# gesture_control_robot_rx.net
KiCad netlist of a schematic drawn in EAGLE
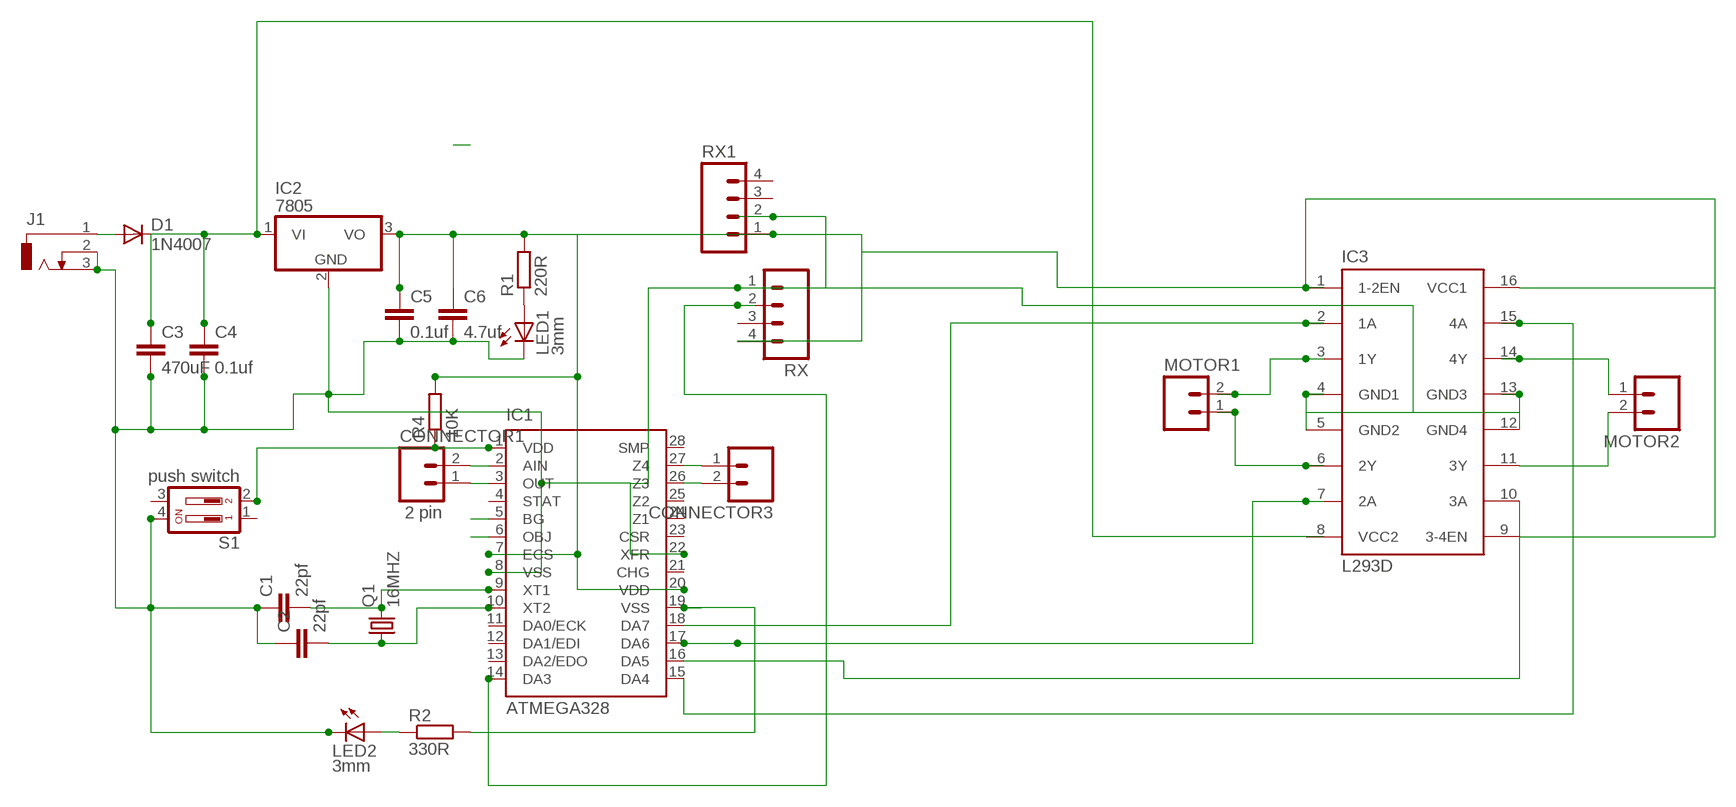
[diagram p0: schematic, sheet 1]

(export (version "E")
  (design (tool "Eeschema 10.0.6"))
  (components
    (comp (ref "C1")
      (value "22pf")
      (footprint "eagle-import:C2.5-2")
      (libsource (lib "eagle-import") (part "C2.5/2"))
    )
    (comp (ref "C2")
      (value "22pf")
      (footprint "eagle-import:C2.5-2")
      (libsource (lib "eagle-import") (part "C2.5/2"))
    )
    (comp (ref "C3")
      (value "470uF")
      (footprint "eagle-import:C2.5-2")
      (libsource (lib "eagle-import") (part "C2.5/2"))
    )
    (comp (ref "C4")
      (value "0.1uf")
      (footprint "eagle-import:C2.5-2")
      (libsource (lib "eagle-import") (part "C2.5/2"))
    )
    (comp (ref "C5")
      (value "0.1uf")
      (footprint "eagle-import:C2.5-2")
      (libsource (lib "eagle-import") (part "C2.5/2"))
    )
    (comp (ref "C6")
      (value "4.7uf")
      (footprint "eagle-import:C2.5-2")
      (libsource (lib "eagle-import") (part "C2.5/2"))
    )
    (comp (ref "CONNECTOR1")
      (value "2 pin")
      (footprint "eagle-import:02P")
      (fields (field (name "OC_FARNELL") "unknown") (field (name "OC_NEWARK") "unknown"))
      (libsource (lib "eagle-import") (part "M02"))
    )
    (comp (ref "CONNECTOR3")
      (value "M02")
      (footprint "eagle-import:02P")
      (fields (field (name "OC_FARNELL") "unknown") (field (name "OC_NEWARK") "unknown"))
      (libsource (lib "eagle-import") (part "M02"))
    )
    (comp (ref "D1")
      (value "1N4007")
      (footprint "eagle-import:DO41-10")
      (libsource (lib "eagle-import") (part "1N4004"))
    )
    (comp (ref "IC1")
      (value "ATMEGA328")
      (footprint "eagle-import:DIL28-3")
      (libsource (lib "eagle-import") (part "QT9701BD"))
    )
    (comp (ref "IC2")
      (value "7805")
      (footprint "eagle-import:TO220V")
      (libsource (lib "eagle-import") (part "78TV6"))
    )
    (comp (ref "IC3")
      (value "L293D")
      (footprint "eagle-import:DIL16")
      (libsource (lib "eagle-import") (part "L293D"))
    )
    (comp (ref "J1")
      (value "DCJ0303")
      (footprint "eagle-import:DCJ0303")
      (libsource (lib "eagle-import") (part "DCJ0303"))
    )
    (comp (ref "LED1")
      (value "3mm")
      (footprint "eagle-import:LED3MM")
      (libsource (lib "eagle-import") (part "LED3MM"))
    )
    (comp (ref "LED2")
      (value "3mm")
      (footprint "eagle-import:LED3MM")
      (libsource (lib "eagle-import") (part "LED3MM"))
    )
    (comp (ref "MOTOR1")
      (value "M02")
      (footprint "eagle-import:02P")
      (fields (field (name "OC_FARNELL") "unknown") (field (name "OC_NEWARK") "unknown"))
      (libsource (lib "eagle-import") (part "M02"))
    )
    (comp (ref "MOTOR2")
      (value "M02")
      (footprint "eagle-import:02P")
      (libsource (lib "eagle-import") (part "M02"))
    )
    (comp (ref "Q1")
      (value "16MHZ")
      (footprint "eagle-import:HC49_S")
      (libsource (lib "eagle-import") (part "CRYSTALHC49S"))
    )
    (comp (ref "R1")
      (value "220R")
      (footprint "eagle-import:0207_10")
      (libsource (lib "eagle-import") (part "R-EU_0207/10"))
    )
    (comp (ref "R2")
      (value "330R")
      (footprint "eagle-import:0207_10")
      (libsource (lib "eagle-import") (part "R-EU_0207/10"))
    )
    (comp (ref "R4")
      (value "10K")
      (footprint "eagle-import:0207_10")
      (libsource (lib "eagle-import") (part "R-EU_0207/10"))
    )
    (comp (ref "RX")
      (value "M04")
      (footprint "eagle-import:04P")
      (libsource (lib "eagle-import") (part "M04"))
    )
    (comp (ref "RX1")
      (value "M04")
      (footprint "eagle-import:04P")
      (fields (field (name "OC_FARNELL") "unknown") (field (name "OC_NEWARK") "unknown"))
      (libsource (lib "eagle-import") (part "M04"))
    )
    (comp (ref "S1")
      (value "push switch")
      (footprint "eagle-import:DP-02")
      (fields (field (name "MPN") "MCDP02"))
      (libsource (lib "eagle-import") (part "DP02"))
    )
  )
  (nets
    (net (code "1") (name "Net-(D1-PadA)") (class "Default")
      (node (ref "D1") (pin "A") (pinfunction "A_A") (pintype "passive"))
      (node (ref "J1") (pin "1") (pinfunction "1_1") (pintype "passive"))
    )
    (net (code "2") (name "Net-(IC1-AIN)") (class "Default")
      (node (ref "CONNECTOR1") (pin "2") (pinfunction "2_2") (pintype "passive"))
      (node (ref "IC1") (pin "2") (pinfunction "AIN_2") (pintype "input"))
    )
    (net (code "3") (name "Net-(IC1-DA3)") (class "Default")
      (node (ref "IC1") (pin "14") (pinfunction "DA3_14") (pintype "output"))
      (node (ref "RX") (pin "2") (pinfunction "2_2") (pintype "passive"))
    )
    (net (code "4") (name "Net-(IC1-DA4)") (class "Default")
      (node (ref "IC1") (pin "15") (pinfunction "DA4_15") (pintype "output"))
      (node (ref "IC3") (pin "15") (pinfunction "4A_15") (pintype "input"))
    )
    (net (code "5") (name "Net-(IC1-DA5)") (class "Default")
      (node (ref "IC1") (pin "16") (pinfunction "DA5_16") (pintype "output"))
      (node (ref "IC3") (pin "10") (pinfunction "3A_10") (pintype "input"))
    )
    (net (code "6") (name "Net-(IC1-DA6)") (class "Default")
      (node (ref "IC1") (pin "17") (pinfunction "DA6_17") (pintype "output"))
      (node (ref "IC3") (pin "7") (pinfunction "2A_7") (pintype "input"))
    )
    (net (code "7") (name "Net-(IC1-DA7)") (class "Default")
      (node (ref "IC1") (pin "18") (pinfunction "DA7_18") (pintype "output"))
      (node (ref "IC3") (pin "2") (pinfunction "1A_2") (pintype "input"))
    )
    (net (code "8") (name "Net-(IC1-ECS)") (class "Default")
      (node (ref "C5") (pin "1") (pinfunction "1_1") (pintype "passive"))
      (node (ref "C6") (pin "1") (pinfunction "1_1") (pintype "passive"))
      (node (ref "IC1") (pin "20") (pinfunction "VDD_20") (pintype "input"))
      (node (ref "IC1") (pin "7") (pinfunction "ECS_7") (pintype "output"))
      (node (ref "IC2") (pin "3") (pinfunction "VO_3") (pintype "passive"))
      (node (ref "IC3") (pin "1") (pinfunction "1-2EN_1") (pintype "input"))
      (node (ref "IC3") (pin "16") (pinfunction "VCC1_16") (pintype "power_in"))
      (node (ref "IC3") (pin "9") (pinfunction "3-4EN_9") (pintype "input"))
      (node (ref "R1") (pin "2") (pinfunction "2_2") (pintype "passive"))
      (node (ref "R4") (pin "2") (pinfunction "2_2") (pintype "passive"))
      (node (ref "RX") (pin "4") (pinfunction "4_4") (pintype "passive"))
      (node (ref "RX1") (pin "1") (pinfunction "1_1") (pintype "passive"))
    )
    (net (code "9") (name "Net-(IC1-OUT)") (class "Default")
      (node (ref "CONNECTOR1") (pin "1") (pinfunction "1_1") (pintype "passive"))
      (node (ref "IC1") (pin "3") (pinfunction "OUT_3") (pintype "output"))
    )
    (net (code "10") (name "Net-(IC1-VDD-Pad1)") (class "Default")
      (node (ref "IC1") (pin "1") (pinfunction "VDD_1") (pintype "input"))
      (node (ref "R4") (pin "1") (pinfunction "1_1") (pintype "passive"))
      (node (ref "S1") (pin "2") (pinfunction "2_2") (pintype "passive"))
    )
    (net (code "11") (name "Net-(IC1-VSS-Pad19)") (class "Default")
      (node (ref "IC1") (pin "19") (pinfunction "VSS_19") (pintype "input"))
      (node (ref "R2") (pin "2") (pinfunction "2_2") (pintype "passive"))
    )
    (net (code "12") (name "Net-(IC1-XFR)") (class "Default")
      (node (ref "C1") (pin "1") (pinfunction "1_1") (pintype "passive"))
      (node (ref "C2") (pin "1") (pinfunction "1_1") (pintype "passive"))
      (node (ref "C3") (pin "2") (pinfunction "2_2") (pintype "passive"))
      (node (ref "C4") (pin "2") (pinfunction "2_2") (pintype "passive"))
      (node (ref "C5") (pin "2") (pinfunction "2_2") (pintype "passive"))
      (node (ref "C6") (pin "2") (pinfunction "2_2") (pintype "passive"))
      (node (ref "IC1") (pin "22") (pinfunction "XFR_22") (pintype "output"))
      (node (ref "IC1") (pin "8") (pinfunction "VSS_8") (pintype "input"))
      (node (ref "IC2") (pin "2") (pinfunction "GND_2") (pintype "passive"))
      (node (ref "IC3") (pin "12") (pinfunction "GND4_12") (pintype "power_in"))
      (node (ref "IC3") (pin "13") (pinfunction "GND3_13") (pintype "power_in"))
      (node (ref "IC3") (pin "4") (pinfunction "GND1_4") (pintype "power_in"))
      (node (ref "IC3") (pin "5") (pinfunction "GND2_5") (pintype "power_in"))
      (node (ref "J1") (pin "2") (pinfunction "2_2") (pintype "passive"))
      (node (ref "J1") (pin "3") (pinfunction "3_3") (pintype "passive"))
      (node (ref "LED1") (pin "K") (pinfunction "C_K") (pintype "passive"))
      (node (ref "LED2") (pin "K") (pinfunction "C_K") (pintype "passive"))
      (node (ref "RX") (pin "1") (pinfunction "1_1") (pintype "passive"))
      (node (ref "RX1") (pin "2") (pinfunction "2_2") (pintype "passive"))
      (node (ref "S1") (pin "4") (pinfunction "4_4") (pintype "passive"))
    )
    (net (code "13") (name "Net-(IC1-XT1)") (class "Default")
      (node (ref "C1") (pin "2") (pinfunction "2_2") (pintype "passive"))
      (node (ref "IC1") (pin "9") (pinfunction "XT1_9") (pintype "input"))
      (node (ref "Q1") (pin "2") (pinfunction "2_2") (pintype "passive"))
    )
    (net (code "14") (name "Net-(IC1-XT2)") (class "Default")
      (node (ref "C2") (pin "2") (pinfunction "2_2") (pintype "passive"))
      (node (ref "IC1") (pin "10") (pinfunction "XT2_10") (pintype "output"))
      (node (ref "Q1") (pin "1") (pinfunction "1_1") (pintype "passive"))
    )
    (net (code "15") (name "Net-(IC1-Z3)") (class "Default")
      (node (ref "CONNECTOR3") (pin "2") (pinfunction "2_2") (pintype "passive"))
      (node (ref "IC1") (pin "26") (pinfunction "Z3_26") (pintype "output"))
    )
    (net (code "16") (name "Net-(IC1-Z4)") (class "Default")
      (node (ref "CONNECTOR3") (pin "1") (pinfunction "1_1") (pintype "passive"))
      (node (ref "IC1") (pin "27") (pinfunction "Z4_27") (pintype "output"))
    )
    (net (code "17") (name "Net-(IC2-VI)") (class "Default")
      (node (ref "C3") (pin "1") (pinfunction "1_1") (pintype "passive"))
      (node (ref "C4") (pin "1") (pinfunction "1_1") (pintype "passive"))
      (node (ref "D1") (pin "C") (pinfunction "C_C") (pintype "passive"))
      (node (ref "IC2") (pin "1") (pinfunction "VI_1") (pintype "input"))
      (node (ref "IC3") (pin "8") (pinfunction "VCC2_8") (pintype "power_in"))
    )
    (net (code "18") (name "Net-(IC3-1Y)") (class "Default")
      (node (ref "IC3") (pin "3") (pinfunction "1Y_3") (pintype "output"))
      (node (ref "MOTOR1") (pin "2") (pinfunction "2_2") (pintype "passive"))
    )
    (net (code "19") (name "Net-(IC3-2Y)") (class "Default")
      (node (ref "IC3") (pin "6") (pinfunction "2Y_6") (pintype "output"))
      (node (ref "MOTOR1") (pin "1") (pinfunction "1_1") (pintype "passive"))
    )
    (net (code "20") (name "Net-(IC3-3Y)") (class "Default")
      (node (ref "IC3") (pin "11") (pinfunction "3Y_11") (pintype "output"))
      (node (ref "MOTOR2") (pin "2") (pinfunction "2_2") (pintype "passive"))
    )
    (net (code "21") (name "Net-(IC3-4Y)") (class "Default")
      (node (ref "IC3") (pin "14") (pinfunction "4Y_14") (pintype "output"))
      (node (ref "MOTOR2") (pin "1") (pinfunction "1_1") (pintype "passive"))
    )
    (net (code "22") (name "Net-(LED1-PadA)") (class "Default")
      (node (ref "LED1") (pin "A") (pinfunction "A_A") (pintype "passive"))
      (node (ref "R1") (pin "1") (pinfunction "1_1") (pintype "passive"))
    )
    (net (code "23") (name "Net-(LED2-PadA)") (class "Default")
      (node (ref "LED2") (pin "A") (pinfunction "A_A") (pintype "passive"))
      (node (ref "R2") (pin "1") (pinfunction "1_1") (pintype "passive"))
    )
    (net (code "24") (name "unconnected-(IC1-BG-Pad5)") (class "Default")
      (node (ref "IC1") (pin "5") (pinfunction "BG_5") (pintype "input"))
    )
    (net (code "25") (name "unconnected-(IC1-CHG-Pad21)") (class "Default")
      (node (ref "IC1") (pin "21") (pinfunction "CHG_21") (pintype "output"))
    )
    (net (code "26") (name "unconnected-(IC1-CSR-Pad23)") (class "Default")
      (node (ref "IC1") (pin "23") (pinfunction "CSR_23") (pintype "output"))
    )
    (net (code "27") (name "unconnected-(IC1-DA0{slash}ECK-Pad11)") (class "Default")
      (node (ref "IC1") (pin "11") (pinfunction "DA0/ECK_11") (pintype "output"))
    )
    (net (code "28") (name "unconnected-(IC1-DA1{slash}EDI-Pad12)") (class "Default")
      (node (ref "IC1") (pin "12") (pinfunction "DA1/EDI_12") (pintype "output"))
    )
    (net (code "29") (name "unconnected-(IC1-DA2{slash}EDO-Pad13)") (class "Default")
      (node (ref "IC1") (pin "13") (pinfunction "DA2/EDO_13") (pintype "output"))
    )
    (net (code "30") (name "unconnected-(IC1-OBJ-Pad6)") (class "Default")
      (node (ref "IC1") (pin "6") (pinfunction "OBJ_6") (pintype "input"))
    )
    (net (code "31") (name "unconnected-(IC1-SMP-Pad28)") (class "Default")
      (node (ref "IC1") (pin "28") (pinfunction "SMP_28") (pintype "output"))
    )
    (net (code "32") (name "unconnected-(IC1-STAT-Pad4)") (class "Default")
      (node (ref "IC1") (pin "4") (pinfunction "STAT_4") (pintype "output"))
    )
    (net (code "33") (name "unconnected-(IC1-Z1-Pad24)") (class "Default")
      (node (ref "IC1") (pin "24") (pinfunction "Z1_24") (pintype "output"))
    )
    (net (code "34") (name "unconnected-(IC1-Z2-Pad25)") (class "Default")
      (node (ref "IC1") (pin "25") (pinfunction "Z2_25") (pintype "output"))
    )
    (net (code "35") (name "unconnected-(RX-Pad3)") (class "Default")
      (node (ref "RX") (pin "3") (pinfunction "3_3") (pintype "passive"))
    )
    (net (code "36") (name "unconnected-(RX1-Pad3)") (class "Default")
      (node (ref "RX1") (pin "3") (pinfunction "3_3") (pintype "passive"))
    )
    (net (code "37") (name "unconnected-(RX1-Pad4)") (class "Default")
      (node (ref "RX1") (pin "4") (pinfunction "4_4") (pintype "passive"))
    )
    (net (code "38") (name "unconnected-(S1-Pad1)") (class "Default")
      (node (ref "S1") (pin "1") (pinfunction "1_1") (pintype "passive"))
    )
    (net (code "39") (name "unconnected-(S1-Pad3)") (class "Default")
      (node (ref "S1") (pin "3") (pinfunction "3_3") (pintype "passive"))
    )
  )
)
